# Measurement.net
KiCad netlist of a schematic drawn in Altium Designer
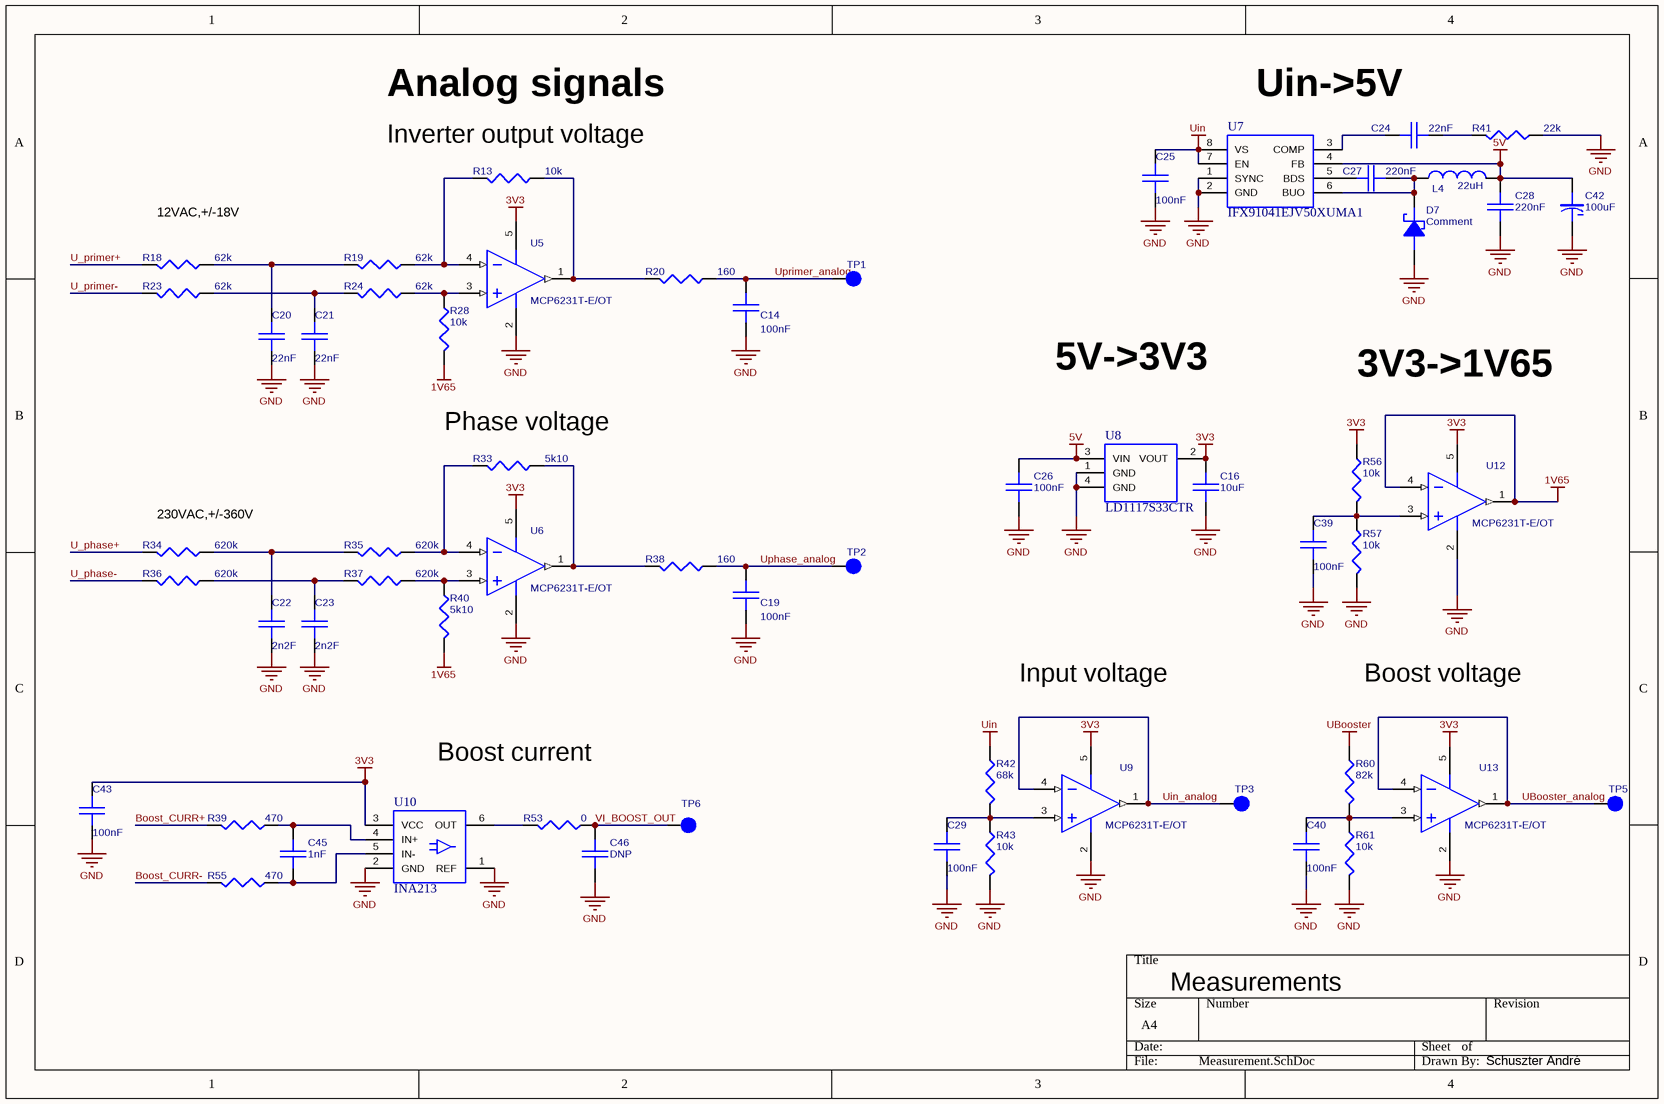
[diagram p0: Measurement.SchDoc]

(export (version "E")
  (design (tool "Eeschema 10.0.6"))
  (components
    (comp (ref "C14")
      (value "100nF")
      (footprint "CAPC2012X06N")
      (description "82-07-32")
      (libsource (lib "PCB_PASSIVE") (part "CAPC"))
    )
    (comp (ref "C16")
      (value "10uF")
      (footprint "CAPC2012X06N")
      (description "82-10-67")
      (libsource (lib "PCB_PASSIVE") (part "CAPC"))
    )
    (comp (ref "C19")
      (value "100nF")
      (footprint "CAPC2012X06N")
      (description "82-07-32")
      (libsource (lib "PCB_PASSIVE") (part "CAPC"))
    )
    (comp (ref "C20")
      (value "22nF")
      (footprint "CAPC2012X06N")
      (description "82-00-77")
      (libsource (lib "PCB_PASSIVE") (part "CAPC"))
    )
    (comp (ref "C21")
      (value "22nF")
      (footprint "CAPC2012X06N")
      (description "82-00-77")
      (libsource (lib "PCB_PASSIVE") (part "CAPC"))
    )
    (comp (ref "C22")
      (value "2n2F")
      (footprint "CAPC2012X06N")
      (description "82-07-24")
      (libsource (lib "PCB_PASSIVE") (part "CAPC"))
    )
    (comp (ref "C23")
      (value "2n2F")
      (footprint "CAPC2012X06N")
      (description "82-07-24")
      (libsource (lib "PCB_PASSIVE") (part "CAPC"))
    )
    (comp (ref "C24")
      (value "22nF")
      (footprint "CAPC2012X06N")
      (description "82-00-77")
      (libsource (lib "PCB_PASSIVE") (part "CAPC"))
    )
    (comp (ref "C25")
      (value "100nF")
      (footprint "CAPC2012X06N")
      (description "82-07-32")
      (libsource (lib "PCB_PASSIVE") (part "CAPC"))
    )
    (comp (ref "C26")
      (value "100nF")
      (footprint "CAPC2012X06N")
      (description "82-07-32")
      (libsource (lib "PCB_PASSIVE") (part "CAPC"))
    )
    (comp (ref "C27")
      (value "220nF")
      (footprint "CAPC2012X06N")
      (description "82-03-85")
      (libsource (lib "PCB_PASSIVE") (part "CAPC"))
    )
    (comp (ref "C28")
      (value "220nF")
      (footprint "CAPC2012X06N")
      (description "82-03-85")
      (libsource (lib "PCB_PASSIVE") (part "CAPC"))
    )
    (comp (ref "C29")
      (value "100nF")
      (footprint "CAPC2012X06N")
      (description "82-07-32")
      (libsource (lib "PCB_PASSIVE") (part "CAPC"))
    )
    (comp (ref "C39")
      (value "100nF")
      (footprint "CAPC2012X06N")
      (description "82-07-32")
      (libsource (lib "PCB_PASSIVE") (part "CAPC"))
    )
    (comp (ref "C40")
      (value "100nF")
      (footprint "CAPC2012X06N")
      (description "82-07-32")
      (libsource (lib "PCB_PASSIVE") (part "CAPC"))
    )
    (comp (ref "C42")
      (value "100uF")
      (footprint "CAPAE6253X61N_Buck")
      (description "2068653")
      (fields (field (name "PART NUMBER") "EDK107M016A9GAA"))
      (libsource (lib "PCB_PASSIVE") (part "CAPAE"))
    )
    (comp (ref "C43")
      (value "100nF")
      (footprint "CAPC2012X06N")
      (description "82-07-32")
      (libsource (lib "PCB_PASSIVE") (part "CAPC"))
    )
    (comp (ref "C45")
      (value "1nF")
      (footprint "CAPC2012X06N")
      (description "82-00-75")
      (libsource (lib "PCB_PASSIVE") (part "CAPC"))
    )
    (comp (ref "C46") (value "DNP") (footprint "CAPC2012X06N") (libsource (lib "PCB_PASSIVE") (part "CAPC")))
    (comp (ref "D7")
      (value "Comment")
      (footprint "Schottky")
      (description "83-02-47")
      (fields (field (name "PART NUMBER") "1A 40V DO-214AC SCH.RECT. SS14"))
      (libsource (lib "PCB_SMALL") (part "DIO_SCHTTKY"))
    )
    (comp (ref "L4")
      (value "22uH")
      (footprint "INDP6060X45N")
      (description "2066673")
      (fields (field (name "PART NUMBER") "LQH6PPN470M43L"))
      (libsource (lib "PCB_PASSIVE") (part "IND"))
    )
    (comp (ref "R13")
      (value "10k")
      (footprint "RESC2012X06N")
      (description "80-10-98")
      (libsource (lib "PCB_PASSIVE") (part "RES_US_HOR"))
    )
    (comp (ref "R18")
      (value "62k")
      (footprint "RESC2012X06N")
      (description "80-11-30")
      (libsource (lib "PCB_PASSIVE") (part "RES_US_HOR"))
    )
    (comp (ref "R19")
      (value "62k")
      (footprint "RESC2012X06N")
      (description "80-11-30")
      (libsource (lib "PCB_PASSIVE") (part "RES_US_HOR"))
    )
    (comp (ref "R20")
      (value "160")
      (footprint "RESC2012X06N")
      (description "81-02-25")
      (libsource (lib "PCB_PASSIVE") (part "RES_US_HOR"))
    )
    (comp (ref "R23")
      (value "62k")
      (footprint "RESC2012X06N")
      (description "80-11-30")
      (libsource (lib "PCB_PASSIVE") (part "RES_US_HOR"))
    )
    (comp (ref "R24")
      (value "62k")
      (footprint "RESC2012X06N")
      (description "80-11-30")
      (libsource (lib "PCB_PASSIVE") (part "RES_US_HOR"))
    )
    (comp (ref "R28")
      (value "10k")
      (footprint "RESC2012X06N")
      (description "80-10-98")
      (libsource (lib "PCB_PASSIVE") (part "RES_US_HOR"))
    )
    (comp (ref "R33")
      (value "5k10")
      (footprint "RESC2012X06N")
      (description "80-14-91")
      (libsource (lib "PCB_PASSIVE") (part "RES_US_HOR"))
    )
    (comp (ref "R34")
      (value "620k")
      (footprint "RESC2012X06N")
      (description "80-15-81")
      (libsource (lib "PCB_PASSIVE") (part "RES_US_HOR"))
    )
    (comp (ref "R35")
      (value "620k")
      (footprint "RESC2012X06N")
      (description "80-15-81")
      (libsource (lib "PCB_PASSIVE") (part "RES_US_HOR"))
    )
    (comp (ref "R36")
      (value "620k")
      (footprint "RESC2012X06N")
      (description "80-15-81")
      (libsource (lib "PCB_PASSIVE") (part "RES_US_HOR"))
    )
    (comp (ref "R37")
      (value "620k")
      (footprint "RESC2012X06N")
      (description "80-15-81")
      (libsource (lib "PCB_PASSIVE") (part "RES_US_HOR"))
    )
    (comp (ref "R38")
      (value "160")
      (footprint "RESC2012X06N")
      (description "81-02-25")
      (libsource (lib "PCB_PASSIVE") (part "RES_US_HOR"))
    )
    (comp (ref "R39")
      (value "470")
      (footprint "RESC2012X06N")
      (description "81-10-83")
      (libsource (lib "PCB_PASSIVE") (part "RES_US_HOR"))
    )
    (comp (ref "R40")
      (value "5k10")
      (footprint "RESC2012X06N")
      (description "80-14-91")
      (libsource (lib "PCB_PASSIVE") (part "RES_US_HOR"))
    )
    (comp (ref "R41")
      (value "22k")
      (footprint "RESC2012X06N")
      (description "81-11-03")
      (libsource (lib "PCB_PASSIVE") (part "RES_US_HOR"))
    )
    (comp (ref "R42")
      (value "68k")
      (footprint "RESC2012X06N")
      (description "80-11-08")
      (libsource (lib "PCB_PASSIVE") (part "RES_US_HOR"))
    )
    (comp (ref "R43")
      (value "10k")
      (footprint "RESC2012X06N")
      (description "80-10-98")
      (libsource (lib "PCB_PASSIVE") (part "RES_US_HOR"))
    )
    (comp (ref "R53")
      (value "0")
      (footprint "RESC2012X06N")
      (description "81-10-02")
      (libsource (lib "PCB_PASSIVE") (part "RES_US_HOR"))
    )
    (comp (ref "R55")
      (value "470")
      (footprint "RESC2012X06N")
      (description "81-10-83")
      (libsource (lib "PCB_PASSIVE") (part "RES_US_HOR"))
    )
    (comp (ref "R56")
      (value "10k")
      (footprint "RESC2012X06N")
      (description "80-10-98")
      (libsource (lib "PCB_PASSIVE") (part "RES_US_HOR"))
    )
    (comp (ref "R57")
      (value "10k")
      (footprint "RESC2012X06N")
      (description "80-10-98")
      (libsource (lib "PCB_PASSIVE") (part "RES_US_HOR"))
    )
    (comp (ref "R60")
      (value "82k")
      (footprint "RESC2012X06N")
      (description "80-11-09")
      (libsource (lib "PCB_PASSIVE") (part "RES_US_HOR"))
    )
    (comp (ref "R61")
      (value "10k")
      (footprint "RESC2012X06N")
      (description "80-10-98")
      (libsource (lib "PCB_PASSIVE") (part "RES_US_HOR"))
    )
    (comp (ref "TP1") (value "Comment") (footprint "TP080") (libsource (lib "PCB_VIRTUAL") (part "TP_SMD")))
    (comp (ref "TP2") (value "Comment") (footprint "TP080") (libsource (lib "PCB_VIRTUAL") (part "TP_SMD")))
    (comp (ref "TP3") (value "Comment") (footprint "TP080") (libsource (lib "PCB_VIRTUAL") (part "TP_SMD")))
    (comp (ref "TP5") (value "Comment") (footprint "TP080") (libsource (lib "PCB_VIRTUAL") (part "TP_SMD")))
    (comp (ref "TP6") (value "Comment") (footprint "TP080") (libsource (lib "PCB_VIRTUAL") (part "TP_SMD")))
    (comp (ref "U5")
      (value "MCP6231T-E/OT")
      (footprint "SOT23-5")
      (description "1840879")
      (libsource (lib "Schlib1") (part "követőerősítő"))
    )
    (comp (ref "U6")
      (value "MCP6231T-E/OT")
      (footprint "SOT23-5")
      (description "1840879")
      (libsource (lib "Schlib1") (part "követőerősítő"))
    )
    (comp (ref "U7")
      (value "IFX91041EJV50XUMA1")
      (footprint "BUCK_CONVERTER")
      (description "2432504")
      (libsource (lib "Schlib1") (part "5V_BUCK"))
    )
    (comp (ref "U8")
      (value "LD1117S33CTR")
      (footprint "SOT230P700X180-4N")
      (description "1467779")
      (libsource (lib "Schlib1") (part "LDO5V-3V3"))
    )
    (comp (ref "U9")
      (value "MCP6231T-E/OT")
      (footprint "SOT23-5")
      (description "1840879")
      (libsource (lib "Schlib1") (part "követőerősítő"))
    )
    (comp (ref "U10")
      (value "INA213")
      (footprint "SOT65P210X110-6N")
      (description "1754261")
      (fields (field (name "PART NUMBER") "INA213AIDCKT"))
      (libsource (lib "Schlib1") (part "INA213"))
    )
    (comp (ref "U12")
      (value "MCP6231T-E/OT")
      (footprint "SOT23-5")
      (description "1840879")
      (libsource (lib "Schlib1") (part "követőerősítő"))
    )
    (comp (ref "U13")
      (value "MCP6231T-E/OT")
      (footprint "SOT23-5")
      (description "1840879")
      (libsource (lib "Schlib1") (part "követőerősítő"))
    )
  )
  (nets
    (net (code "1") (name "/Boost_CURR+") (class "Default")
      (node (ref "R39") (pin "2") (pinfunction "2_2") (pintype "passive"))
    )
    (net (code "2") (name "/Boost_CURR-") (class "Default")
      (node (ref "R55") (pin "2") (pinfunction "2_2") (pintype "passive"))
    )
    (net (code "3") (name "/UBooster_analog") (class "Default")
      (node (ref "TP5") (pin "1") (pinfunction "Pin1_1") (pintype "passive"))
      (node (ref "U13") (pin "1") (pinfunction "OUT_1") (pintype "output"))
      (node (ref "U13") (pin "4") (pinfunction "IN-_4") (pintype "input"))
    )
    (net (code "4") (name "/U_phase+") (class "Default")
      (node (ref "R34") (pin "2") (pinfunction "2_2") (pintype "passive"))
    )
    (net (code "5") (name "/U_phase-") (class "Default")
      (node (ref "R36") (pin "2") (pinfunction "2_2") (pintype "passive"))
    )
    (net (code "6") (name "/U_primer+") (class "Default")
      (node (ref "R18") (pin "2") (pinfunction "2_2") (pintype "passive"))
    )
    (net (code "7") (name "/U_primer-") (class "Default")
      (node (ref "R23") (pin "2") (pinfunction "2_2") (pintype "passive"))
    )
    (net (code "8") (name "/Uin_analog") (class "Default")
      (node (ref "TP3") (pin "1") (pinfunction "Pin1_1") (pintype "passive"))
      (node (ref "U9") (pin "1") (pinfunction "OUT_1") (pintype "output"))
      (node (ref "U9") (pin "4") (pinfunction "IN-_4") (pintype "input"))
    )
    (net (code "9") (name "/Uphase_analog") (class "Default")
      (node (ref "C19") (pin "1") (pinfunction "1_1") (pintype "passive"))
      (node (ref "R38") (pin "1") (pinfunction "1_1") (pintype "passive"))
      (node (ref "TP2") (pin "1") (pinfunction "Pin1_1") (pintype "passive"))
    )
    (net (code "10") (name "/Uprimer_analog") (class "Default")
      (node (ref "C14") (pin "1") (pinfunction "1_1") (pintype "passive"))
      (node (ref "R20") (pin "1") (pinfunction "1_1") (pintype "passive"))
      (node (ref "TP1") (pin "1") (pinfunction "Pin1_1") (pintype "passive"))
    )
    (net (code "11") (name "/VI_BOOST_OUT") (class "Default")
      (node (ref "C46") (pin "2") (pinfunction "2_2") (pintype "passive"))
      (node (ref "R53") (pin "1") (pinfunction "1_1") (pintype "passive"))
      (node (ref "TP6") (pin "1") (pinfunction "Pin1_1") (pintype "passive"))
    )
    (net (code "12") (name "1V65") (class "Default")
      (node (ref "R28") (pin "2") (pinfunction "2_2") (pintype "passive"))
      (node (ref "R40") (pin "2") (pinfunction "2_2") (pintype "passive"))
      (node (ref "U12") (pin "1") (pinfunction "OUT_1") (pintype "output"))
      (node (ref "U12") (pin "4") (pinfunction "IN-_4") (pintype "input"))
    )
    (net (code "13") (name "3V3") (class "Default")
      (node (ref "C16") (pin "2") (pinfunction "2_2") (pintype "passive"))
      (node (ref "C43") (pin "1") (pinfunction "1_1") (pintype "passive"))
      (node (ref "R56") (pin "1") (pinfunction "1_1") (pintype "passive"))
      (node (ref "U10") (pin "3") (pinfunction "VCC_3") (pintype "passive"))
      (node (ref "U12") (pin "5") (pinfunction "VDD_5") (pintype "power_in"))
      (node (ref "U13") (pin "5") (pinfunction "VDD_5") (pintype "power_in"))
      (node (ref "U5") (pin "5") (pinfunction "VDD_5") (pintype "power_in"))
      (node (ref "U6") (pin "5") (pinfunction "VDD_5") (pintype "power_in"))
      (node (ref "U8") (pin "2") (pinfunction "VOUT_2") (pintype "passive"))
      (node (ref "U9") (pin "5") (pinfunction "VDD_5") (pintype "power_in"))
    )
    (net (code "14") (name "5V") (class "Default")
      (node (ref "C26") (pin "2") (pinfunction "2_2") (pintype "passive"))
      (node (ref "C28") (pin "2") (pinfunction "2_2") (pintype "passive"))
      (node (ref "C42") (pin "1") (pinfunction "P_1") (pintype "passive"))
      (node (ref "L4") (pin "2") (pinfunction "2_2") (pintype "passive"))
      (node (ref "U7") (pin "4") (pinfunction "FB_4") (pintype "passive"))
      (node (ref "U8") (pin "3") (pinfunction "VIN_3") (pintype "passive"))
    )
    (net (code "15") (name "GND") (class "Default")
      (node (ref "C14") (pin "2") (pinfunction "2_2") (pintype "passive"))
      (node (ref "C16") (pin "1") (pinfunction "1_1") (pintype "passive"))
      (node (ref "C19") (pin "2") (pinfunction "2_2") (pintype "passive"))
      (node (ref "C20") (pin "2") (pinfunction "2_2") (pintype "passive"))
      (node (ref "C21") (pin "2") (pinfunction "2_2") (pintype "passive"))
      (node (ref "C22") (pin "2") (pinfunction "2_2") (pintype "passive"))
      (node (ref "C23") (pin "2") (pinfunction "2_2") (pintype "passive"))
      (node (ref "C25") (pin "2") (pinfunction "2_2") (pintype "passive"))
      (node (ref "C26") (pin "1") (pinfunction "1_1") (pintype "passive"))
      (node (ref "C28") (pin "1") (pinfunction "1_1") (pintype "passive"))
      (node (ref "C29") (pin "2") (pinfunction "2_2") (pintype "passive"))
      (node (ref "C39") (pin "2") (pinfunction "2_2") (pintype "passive"))
      (node (ref "C40") (pin "2") (pinfunction "2_2") (pintype "passive"))
      (node (ref "C42") (pin "2") (pinfunction "N_2") (pintype "passive"))
      (node (ref "C43") (pin "2") (pinfunction "2_2") (pintype "passive"))
      (node (ref "C46") (pin "1") (pinfunction "1_1") (pintype "passive"))
      (node (ref "D7") (pin "A") (pinfunction "A_A") (pintype "passive"))
      (node (ref "R41") (pin "1") (pinfunction "1_1") (pintype "passive"))
      (node (ref "R43") (pin "2") (pinfunction "2_2") (pintype "passive"))
      (node (ref "R57") (pin "2") (pinfunction "2_2") (pintype "passive"))
      (node (ref "R61") (pin "2") (pinfunction "2_2") (pintype "passive"))
      (node (ref "U10") (pin "1") (pinfunction "REF_1") (pintype "passive"))
      (node (ref "U10") (pin "2") (pinfunction "GND_2") (pintype "passive"))
      (node (ref "U12") (pin "2") (pinfunction "GND_2") (pintype "power_in"))
      (node (ref "U13") (pin "2") (pinfunction "GND_2") (pintype "power_in"))
      (node (ref "U5") (pin "2") (pinfunction "GND_2") (pintype "power_in"))
      (node (ref "U6") (pin "2") (pinfunction "GND_2") (pintype "power_in"))
      (node (ref "U7") (pin "1") (pinfunction "SYNC_1") (pintype "passive"))
      (node (ref "U7") (pin "2") (pinfunction "GND_2") (pintype "passive"))
      (node (ref "U8") (pin "1") (pinfunction "GND_1") (pintype "passive"))
      (node (ref "U8") (pin "4") (pinfunction "GND_4") (pintype "passive"))
      (node (ref "U9") (pin "2") (pinfunction "GND_2") (pintype "power_in"))
    )
    (net (code "16") (name "Net-(C20-Pad1)") (class "Default")
      (node (ref "C20") (pin "1") (pinfunction "1_1") (pintype "passive"))
      (node (ref "R18") (pin "1") (pinfunction "1_1") (pintype "passive"))
      (node (ref "R19") (pin "2") (pinfunction "2_2") (pintype "passive"))
    )
    (net (code "17") (name "Net-(C21-Pad1)") (class "Default")
      (node (ref "C21") (pin "1") (pinfunction "1_1") (pintype "passive"))
      (node (ref "R23") (pin "1") (pinfunction "1_1") (pintype "passive"))
      (node (ref "R24") (pin "2") (pinfunction "2_2") (pintype "passive"))
    )
    (net (code "18") (name "Net-(C22-Pad1)") (class "Default")
      (node (ref "C22") (pin "1") (pinfunction "1_1") (pintype "passive"))
      (node (ref "R34") (pin "1") (pinfunction "1_1") (pintype "passive"))
      (node (ref "R35") (pin "2") (pinfunction "2_2") (pintype "passive"))
    )
    (net (code "19") (name "Net-(C23-Pad1)") (class "Default")
      (node (ref "C23") (pin "1") (pinfunction "1_1") (pintype "passive"))
      (node (ref "R36") (pin "1") (pinfunction "1_1") (pintype "passive"))
      (node (ref "R37") (pin "2") (pinfunction "2_2") (pintype "passive"))
    )
    (net (code "20") (name "Net-(C24-Pad2)") (class "Default")
      (node (ref "C24") (pin "2") (pinfunction "2_2") (pintype "passive"))
      (node (ref "R41") (pin "2") (pinfunction "2_2") (pintype "passive"))
    )
    (net (code "21") (name "Net-(U5-IN+)") (class "Default")
      (node (ref "R24") (pin "1") (pinfunction "1_1") (pintype "passive"))
      (node (ref "R28") (pin "1") (pinfunction "1_1") (pintype "passive"))
      (node (ref "U5") (pin "3") (pinfunction "IN+_3") (pintype "input"))
    )
    (net (code "22") (name "Net-(U5-IN-)") (class "Default")
      (node (ref "R13") (pin "2") (pinfunction "2_2") (pintype "passive"))
      (node (ref "R19") (pin "1") (pinfunction "1_1") (pintype "passive"))
      (node (ref "U5") (pin "4") (pinfunction "IN-_4") (pintype "input"))
    )
    (net (code "23") (name "Net-(U5-OUT)") (class "Default")
      (node (ref "R13") (pin "1") (pinfunction "1_1") (pintype "passive"))
      (node (ref "R20") (pin "2") (pinfunction "2_2") (pintype "passive"))
      (node (ref "U5") (pin "1") (pinfunction "OUT_1") (pintype "output"))
    )
    (net (code "24") (name "Net-(U6-IN+)") (class "Default")
      (node (ref "R37") (pin "1") (pinfunction "1_1") (pintype "passive"))
      (node (ref "R40") (pin "1") (pinfunction "1_1") (pintype "passive"))
      (node (ref "U6") (pin "3") (pinfunction "IN+_3") (pintype "input"))
    )
    (net (code "25") (name "Net-(U6-IN-)") (class "Default")
      (node (ref "R33") (pin "2") (pinfunction "2_2") (pintype "passive"))
      (node (ref "R35") (pin "1") (pinfunction "1_1") (pintype "passive"))
      (node (ref "U6") (pin "4") (pinfunction "IN-_4") (pintype "input"))
    )
    (net (code "26") (name "Net-(U6-OUT)") (class "Default")
      (node (ref "R33") (pin "1") (pinfunction "1_1") (pintype "passive"))
      (node (ref "R38") (pin "2") (pinfunction "2_2") (pintype "passive"))
      (node (ref "U6") (pin "1") (pinfunction "OUT_1") (pintype "output"))
    )
    (net (code "27") (name "Net-(U7-BDS)") (class "Default")
      (node (ref "C27") (pin "1") (pinfunction "1_1") (pintype "passive"))
      (node (ref "U7") (pin "5") (pinfunction "BDS_5") (pintype "passive"))
    )
    (net (code "28") (name "Net-(U7-BUO)") (class "Default")
      (node (ref "C27") (pin "2") (pinfunction "2_2") (pintype "passive"))
      (node (ref "D7") (pin "C") (pinfunction "C_C") (pintype "passive"))
      (node (ref "L4") (pin "1") (pinfunction "1_1") (pintype "passive"))
      (node (ref "U7") (pin "6") (pinfunction "BUO_6") (pintype "passive"))
    )
    (net (code "29") (name "Net-(U7-COMP)") (class "Default")
      (node (ref "C24") (pin "1") (pinfunction "1_1") (pintype "passive"))
      (node (ref "U7") (pin "3") (pinfunction "COMP_3") (pintype "passive"))
    )
    (net (code "30") (name "Net-(U9-IN+)") (class "Default")
      (node (ref "C29") (pin "1") (pinfunction "1_1") (pintype "passive"))
      (node (ref "R42") (pin "2") (pinfunction "2_2") (pintype "passive"))
      (node (ref "R43") (pin "1") (pinfunction "1_1") (pintype "passive"))
      (node (ref "U9") (pin "3") (pinfunction "IN+_3") (pintype "input"))
    )
    (net (code "31") (name "Net-(U10-IN+)") (class "Default")
      (node (ref "C45") (pin "2") (pinfunction "2_2") (pintype "passive"))
      (node (ref "R39") (pin "1") (pinfunction "1_1") (pintype "passive"))
      (node (ref "U10") (pin "4") (pinfunction "IN+_4") (pintype "passive"))
    )
    (net (code "32") (name "Net-(U10-IN-)") (class "Default")
      (node (ref "C45") (pin "1") (pinfunction "1_1") (pintype "passive"))
      (node (ref "R55") (pin "1") (pinfunction "1_1") (pintype "passive"))
      (node (ref "U10") (pin "5") (pinfunction "IN-_5") (pintype "passive"))
    )
    (net (code "33") (name "Net-(U10-OUT)") (class "Default")
      (node (ref "R53") (pin "2") (pinfunction "2_2") (pintype "passive"))
      (node (ref "U10") (pin "6") (pinfunction "OUT_6") (pintype "passive"))
    )
    (net (code "34") (name "Net-(U12-IN+)") (class "Default")
      (node (ref "C39") (pin "1") (pinfunction "1_1") (pintype "passive"))
      (node (ref "R56") (pin "2") (pinfunction "2_2") (pintype "passive"))
      (node (ref "R57") (pin "1") (pinfunction "1_1") (pintype "passive"))
      (node (ref "U12") (pin "3") (pinfunction "IN+_3") (pintype "input"))
    )
    (net (code "35") (name "Net-(U13-IN+)") (class "Default")
      (node (ref "C40") (pin "1") (pinfunction "1_1") (pintype "passive"))
      (node (ref "R60") (pin "2") (pinfunction "2_2") (pintype "passive"))
      (node (ref "R61") (pin "1") (pinfunction "1_1") (pintype "passive"))
      (node (ref "U13") (pin "3") (pinfunction "IN+_3") (pintype "input"))
    )
    (net (code "36") (name "UBooster") (class "Default")
      (node (ref "R60") (pin "1") (pinfunction "1_1") (pintype "passive"))
    )
    (net (code "37") (name "Uin") (class "Default")
      (node (ref "C25") (pin "1") (pinfunction "1_1") (pintype "passive"))
      (node (ref "R42") (pin "1") (pinfunction "1_1") (pintype "passive"))
      (node (ref "U7") (pin "7") (pinfunction "EN_7") (pintype "passive"))
      (node (ref "U7") (pin "8") (pinfunction "VS_8") (pintype "passive"))
    )
  )
)
